# TN_Deck__Display_Board.net
KiCad netlist of a schematic drawn in EAGLE
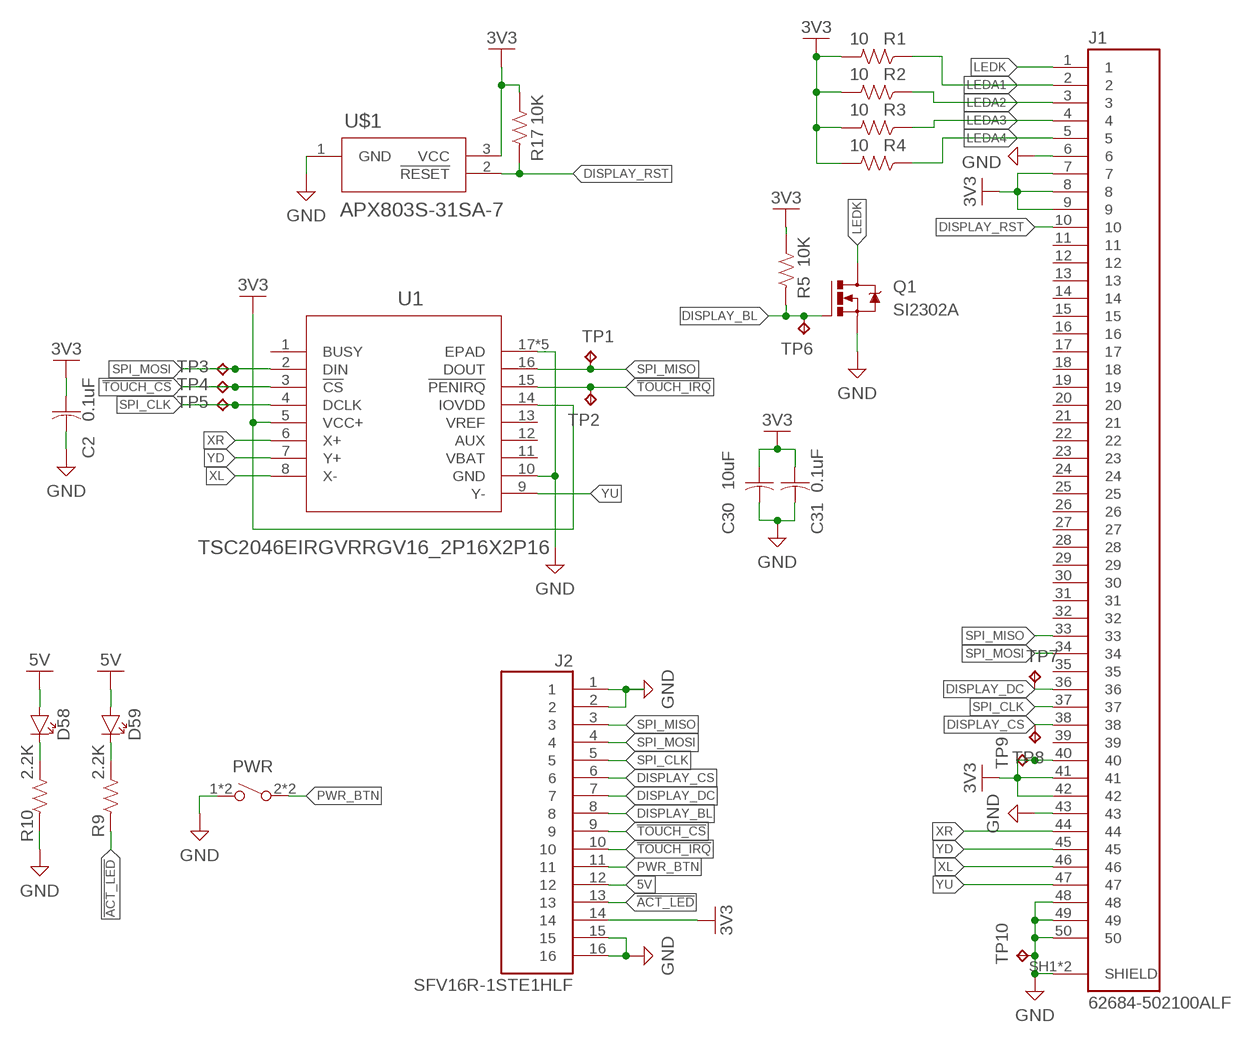
[diagram p0: schematic, sheet 1]

(export (version "E")
  (design (tool "Eeschema 10.0.6"))
  (components
    (comp (ref "C2")
      (value "0.1uF")
      (footprint "eagle-import:CAPC1608X85")
      (fields (field (name "VENDOR") "Digikey") (field (name "VPN") "399-C0603C104K3RACTUCT-ND"))
      (libsource (lib "eagle-import") (part "C-USCHIP-0603(1608-METRIC)_"))
    )
    (comp (ref "C30")
      (value "10uF")
      (footprint "eagle-import:CAPC2012X110")
      (fields (field (name "VENDOR") "Digikey") (field (name "VPN") "1292-0805X106K250CT-ND"))
      (libsource (lib "eagle-import") (part "C-USCHIP-0805(2012-METRIC)_"))
    )
    (comp (ref "C31")
      (value "0.1uF")
      (footprint "eagle-import:CAPC1608X85")
      (fields (field (name "VENDOR") "Digikey") (field (name "VPN") "399-C0603C104K3RACTUCT-ND"))
      (libsource (lib "eagle-import") (part "C-USCHIP-0603(1608-METRIC)_"))
    )
    (comp (ref "D58")
      (value "CHIP-FLAT-G_0603-0.80MM")
      (footprint "eagle-import:LEDC1608X80N_FLAT-G")
      (fields (field (name "VENDOR") "Digikey") (field (name "VPN") "732-4980-1-ND"))
      (libsource (lib "eagle-import") (part "CHIP-FLAT-G_0603-0.80MM"))
    )
    (comp (ref "D59")
      (value "CHIP-FLAT-G_0603-0.80MM")
      (footprint "eagle-import:LEDC1608X80N_FLAT-G")
      (fields (field (name "VENDOR") "Digikey") (field (name "VPN") "732-4980-1-ND"))
      (libsource (lib "eagle-import") (part "CHIP-FLAT-G_0603-0.80MM"))
    )
    (comp (ref "J1")
      (value "62684-502100ALF")
      (footprint "eagle-import:AMPHENOL_62684-502100ALF")
      (fields
        (field (name "MANUFACTURER") "Amphenol")
        (field (name "VENDOR") "Digikey")
        (field (name "VPN") "609-1202-1-ND")
      )
      (libsource (lib "eagle-import") (part "62684-502100ALF"))
    )
    (comp (ref "J2")
      (value "SFV16R-1STE1HLF")
      (footprint "eagle-import:AMPHENOL_SFV16R-1STE1HLF")
      (fields
        (field (name "MANUFACTURER") "Amphenol")
        (field (name "VENDOR") "Digikey")
        (field (name "VPN") "609-4313-1-ND")
      )
      (libsource (lib "eagle-import") (part "SFV16R-1STE1HLF"))
    )
    (comp (ref "PWR")
      (value "SPST-NO_SWITCH_KMR2")
      (footprint "eagle-import:KMR2")
      (fields
        (field (name "MANUFACTURER") "C&K")
        (field (name "MPN") "KMR211G LFS")
        (field (name "VENDOR") "Digikey")
        (field (name "VPN") "401-1426-1-ND")
      )
      (libsource (lib "eagle-import") (part "SPST-NO_SWITCH_KMR2"))
    )
    (comp (ref "Q1")
      (value "SI2302A")
      (footprint "eagle-import:SOT23")
      (fields (field (name "VENDOR") "Digikey") (field (name "VPN") "4518-SI2302ACT-ND"))
      (libsource (lib "eagle-import") (part "NMOSFETSOT23-GSD_"))
    )
    (comp (ref "R1")
      (value "10")
      (footprint "eagle-import:RESC1608X60")
      (fields (field (name "VENDOR") "Digikey") (field (name "VPN") "541-10.0HCT-ND"))
      (libsource (lib "eagle-import") (part "R-USCHIP-0603(1608-METRIC)_"))
    )
    (comp (ref "R2")
      (value "10")
      (footprint "eagle-import:RESC1608X60")
      (fields (field (name "VENDOR") "Digikey") (field (name "VPN") "541-10.0HCT-ND"))
      (libsource (lib "eagle-import") (part "R-USCHIP-0603(1608-METRIC)_"))
    )
    (comp (ref "R3")
      (value "10")
      (footprint "eagle-import:RESC1608X60")
      (fields (field (name "VENDOR") "Digikey") (field (name "VPN") "541-10.0HCT-ND"))
      (libsource (lib "eagle-import") (part "R-USCHIP-0603(1608-METRIC)_"))
    )
    (comp (ref "R4")
      (value "10")
      (footprint "eagle-import:RESC1608X60")
      (fields (field (name "VENDOR") "Digikey") (field (name "VPN") "541-10.0HCT-ND"))
      (libsource (lib "eagle-import") (part "R-USCHIP-0603(1608-METRIC)_"))
    )
    (comp (ref "R5")
      (value "10K")
      (footprint "eagle-import:RESC1608X60")
      (fields (field (name "VENDOR") "Digikey") (field (name "VPN") "541-10.0KHCT-ND"))
      (libsource (lib "eagle-import") (part "R-USCHIP-0603(1608-METRIC)_"))
    )
    (comp (ref "R9")
      (value "2.2K")
      (footprint "eagle-import:RESC1608X60")
      (fields (field (name "VENDOR") "Digikey") (field (name "VPN") "541-2.20KHCT-ND"))
      (libsource (lib "eagle-import") (part "R-USCHIP-0603(1608-METRIC)_"))
    )
    (comp (ref "R10")
      (value "2.2K")
      (footprint "eagle-import:RESC1608X60")
      (fields (field (name "VENDOR") "Digikey") (field (name "VPN") "541-2.20KHCT-ND"))
      (libsource (lib "eagle-import") (part "R-USCHIP-0603(1608-METRIC)_"))
    )
    (comp (ref "R17")
      (value "10K")
      (footprint "eagle-import:RESC1608X60")
      (fields (field (name "VENDOR") "Digikey") (field (name "VPN") "541-10.0KHCT-ND"))
      (libsource (lib "eagle-import") (part "R-USCHIP-0603(1608-METRIC)_"))
    )
    (comp (ref "TP1")
      (value "TPB1,27")
      (footprint "eagle-import:B1,27")
      (libsource (lib "eagle-import") (part "TPB1,27"))
    )
    (comp (ref "TP2")
      (value "TPB1,27")
      (footprint "eagle-import:B1,27")
      (libsource (lib "eagle-import") (part "TPB1,27"))
    )
    (comp (ref "TP3")
      (value "TPB1,27")
      (footprint "eagle-import:B1,27")
      (libsource (lib "eagle-import") (part "TPB1,27"))
    )
    (comp (ref "TP4")
      (value "TPB1,27")
      (footprint "eagle-import:B1,27")
      (libsource (lib "eagle-import") (part "TPB1,27"))
    )
    (comp (ref "TP5")
      (value "TPB1,27")
      (footprint "eagle-import:B1,27")
      (libsource (lib "eagle-import") (part "TPB1,27"))
    )
    (comp (ref "TP6")
      (value "TPB1,27")
      (footprint "eagle-import:B1,27")
      (libsource (lib "eagle-import") (part "TPB1,27"))
    )
    (comp (ref "TP7")
      (value "TPB1,27")
      (footprint "eagle-import:B1,27")
      (libsource (lib "eagle-import") (part "TPB1,27"))
    )
    (comp (ref "TP8")
      (value "TPB1,27")
      (footprint "eagle-import:B1,27")
      (libsource (lib "eagle-import") (part "TPB1,27"))
    )
    (comp (ref "TP9")
      (value "TPB1,27")
      (footprint "eagle-import:B1,27")
      (libsource (lib "eagle-import") (part "TPB1,27"))
    )
    (comp (ref "TP10")
      (value "TPB1,27")
      (footprint "eagle-import:B1,27")
      (libsource (lib "eagle-import") (part "TPB1,27"))
    )
    (comp (ref "U$1")
      (value "APX803S-31SA-7")
      (footprint "eagle-import:SOT-23_DIO")
      (fields (field (name "VENDOR") "Digikey") (field (name "VPN") "APX803S-31SA-7DICT-ND"))
      (libsource (lib "eagle-import") (part "APX803S-31SA-7"))
    )
    (comp (ref "U1")
      (value "TSC2046EIRGVRRGV16_2P16X2P16")
      (footprint "eagle-import:RGV16_2P16X2P16")
      (fields
        (field (name "MANUFACTURER_PART_NUMBER") "TSC2046EIRGVR")
        (field (name "VENDOR") "Digikey")
        (field (name "VPN") "296-46257-1-ND")
        (field (name "COPYRIGHT") "Copyright (C) 2026 Ultra Librarian. All rights reserved.")
      )
      (libsource (lib "eagle-import") (part "TSC2046EIRGVRRGV16_2P16X2P16"))
    )
  )
  (nets
    (net (code "1") (name "/VREF") (class "Default")
      (node (ref "U1") (pin "13") (pinfunction "VREF_13") (pintype "power_in"))
    )
    (net (code "2") (name "/~{ACT_LED}") (class "Default")
      (node (ref "J2") (pin "13") (pinfunction "13_13") (pintype "passive"))
      (node (ref "R9") (pin "1") (pinfunction "1_1") (pintype "passive"))
    )
    (net (code "3") (name "/~{TOUCH_CS}") (class "Default")
      (node (ref "J2") (pin "9") (pinfunction "9_9") (pintype "passive"))
      (node (ref "TP4") (pin "TP") (pinfunction "TP_TP") (pintype "input"))
      (node (ref "U1") (pin "3") (pinfunction "~{CS}_3") (pintype "input"))
    )
    (net (code "4") (name "/~{TOUCH_IRQ}") (class "Default")
      (node (ref "J2") (pin "10") (pinfunction "10_10") (pintype "passive"))
      (node (ref "TP2") (pin "TP") (pinfunction "TP_TP") (pintype "input"))
      (node (ref "U1") (pin "15") (pinfunction "~{PENIRQ}_15") (pintype "input"))
    )
    (net (code "5") (name "3V3") (class "Default")
      (node (ref "C2") (pin "1") (pinfunction "1_1") (pintype "passive"))
      (node (ref "C30") (pin "1") (pinfunction "1_1") (pintype "passive"))
      (node (ref "C31") (pin "1") (pinfunction "1_1") (pintype "passive"))
      (node (ref "J1") (pin "40") (pinfunction "40_40") (pintype "passive"))
      (node (ref "J1") (pin "41") (pinfunction "41_41") (pintype "passive"))
      (node (ref "J1") (pin "42") (pinfunction "42_42") (pintype "passive"))
      (node (ref "J1") (pin "7") (pinfunction "7_7") (pintype "passive"))
      (node (ref "J1") (pin "8") (pinfunction "8_8") (pintype "passive"))
      (node (ref "J1") (pin "9") (pinfunction "9_9") (pintype "passive"))
      (node (ref "J2") (pin "14") (pinfunction "14_14") (pintype "passive"))
      (node (ref "R1") (pin "2") (pinfunction "2_2") (pintype "passive"))
      (node (ref "R17") (pin "2") (pinfunction "2_2") (pintype "passive"))
      (node (ref "R2") (pin "2") (pinfunction "2_2") (pintype "passive"))
      (node (ref "R3") (pin "2") (pinfunction "2_2") (pintype "passive"))
      (node (ref "R4") (pin "2") (pinfunction "2_2") (pintype "passive"))
      (node (ref "R5") (pin "2") (pinfunction "2_2") (pintype "passive"))
      (node (ref "TP9") (pin "TP") (pinfunction "TP_TP") (pintype "input"))
      (node (ref "U$1") (pin "3") (pinfunction "VCC_3") (pintype "power_in"))
      (node (ref "U1") (pin "14") (pinfunction "IOVDD_14") (pintype "bidirectional"))
      (node (ref "U1") (pin "5") (pinfunction "VCC+_5") (pintype "power_in"))
    )
    (net (code "6") (name "5V") (class "Default")
      (node (ref "D58") (pin "A") (pinfunction "A_A") (pintype "passive"))
      (node (ref "D59") (pin "A") (pinfunction "A_A") (pintype "passive"))
      (node (ref "J2") (pin "12") (pinfunction "12_12") (pintype "passive"))
    )
    (net (code "7") (name "DISPLAY_BL") (class "Default")
      (node (ref "J2") (pin "8") (pinfunction "8_8") (pintype "passive"))
      (node (ref "Q1") (pin "1") (pinfunction "G_1") (pintype "passive"))
      (node (ref "R5") (pin "1") (pinfunction "1_1") (pintype "passive"))
      (node (ref "TP6") (pin "TP") (pinfunction "TP_TP") (pintype "input"))
    )
    (net (code "8") (name "DISPLAY_CS") (class "Default")
      (node (ref "J1") (pin "38") (pinfunction "38_38") (pintype "passive"))
      (node (ref "J2") (pin "6") (pinfunction "6_6") (pintype "passive"))
      (node (ref "TP8") (pin "TP") (pinfunction "TP_TP") (pintype "input"))
    )
    (net (code "9") (name "DISPLAY_DC") (class "Default")
      (node (ref "J1") (pin "36") (pinfunction "36_36") (pintype "passive"))
      (node (ref "J2") (pin "7") (pinfunction "7_7") (pintype "passive"))
      (node (ref "TP7") (pin "TP") (pinfunction "TP_TP") (pintype "input"))
    )
    (net (code "10") (name "DISPLAY_RST") (class "Default")
      (node (ref "J1") (pin "10") (pinfunction "10_10") (pintype "passive"))
      (node (ref "R17") (pin "1") (pinfunction "1_1") (pintype "passive"))
      (node (ref "U$1") (pin "2") (pinfunction "~{RESET}_2") (pintype "output"))
    )
    (net (code "11") (name "GND") (class "Default")
      (node (ref "C2") (pin "2") (pinfunction "2_2") (pintype "passive"))
      (node (ref "C30") (pin "2") (pinfunction "2_2") (pintype "passive"))
      (node (ref "C31") (pin "2") (pinfunction "2_2") (pintype "passive"))
      (node (ref "J1") (pin "43") (pinfunction "43_43") (pintype "passive"))
      (node (ref "J1") (pin "48") (pinfunction "48_48") (pintype "passive"))
      (node (ref "J1") (pin "49") (pinfunction "49_49") (pintype "passive"))
      (node (ref "J1") (pin "50") (pinfunction "50_50") (pintype "passive"))
      (node (ref "J1") (pin "6") (pinfunction "6_6") (pintype "passive"))
      (node (ref "J1") (pin "SH1") (pinfunction "SHIELD_SH1") (pintype "passive"))
      (node (ref "J1") (pin "SH2") (pinfunction "SHIELD_SH2") (pintype "passive"))
      (node (ref "J2") (pin "1") (pinfunction "1_1") (pintype "passive"))
      (node (ref "J2") (pin "15") (pinfunction "15_15") (pintype "passive"))
      (node (ref "J2") (pin "16") (pinfunction "16_16") (pintype "passive"))
      (node (ref "J2") (pin "2") (pinfunction "2_2") (pintype "passive"))
      (node (ref "PWR") (pin "1") (pinfunction "1_1") (pintype "passive"))
      (node (ref "PWR") (pin "4") (pinfunction "1_4") (pintype "passive"))
      (node (ref "Q1") (pin "2") (pinfunction "S_2") (pintype "passive"))
      (node (ref "R10") (pin "1") (pinfunction "1_1") (pintype "passive"))
      (node (ref "TP10") (pin "TP") (pinfunction "TP_TP") (pintype "input"))
      (node (ref "U$1") (pin "1") (pinfunction "GND_1") (pintype "power_in"))
      (node (ref "U1") (pin "10") (pinfunction "GND_10") (pintype "power_in"))
      (node (ref "U1") (pin "17") (pinfunction "EPAD_17") (pintype "passive"))
      (node (ref "U1") (pin "V") (pinfunction "EPAD_V") (pintype "passive"))
      (node (ref "U1") (pin "V_1") (pinfunction "EPAD_V_1") (pintype "passive"))
      (node (ref "U1") (pin "V_2") (pinfunction "EPAD_V_2") (pintype "passive"))
      (node (ref "U1") (pin "V_3") (pinfunction "EPAD_V_3") (pintype "passive"))
    )
    (net (code "12") (name "LEDA1") (class "Default")
      (node (ref "J1") (pin "2") (pinfunction "2_2") (pintype "passive"))
      (node (ref "R1") (pin "1") (pinfunction "1_1") (pintype "passive"))
    )
    (net (code "13") (name "LEDA2") (class "Default")
      (node (ref "J1") (pin "3") (pinfunction "3_3") (pintype "passive"))
      (node (ref "R2") (pin "1") (pinfunction "1_1") (pintype "passive"))
    )
    (net (code "14") (name "LEDA3") (class "Default")
      (node (ref "J1") (pin "4") (pinfunction "4_4") (pintype "passive"))
      (node (ref "R3") (pin "1") (pinfunction "1_1") (pintype "passive"))
    )
    (net (code "15") (name "LEDA4") (class "Default")
      (node (ref "J1") (pin "5") (pinfunction "5_5") (pintype "passive"))
      (node (ref "R4") (pin "1") (pinfunction "1_1") (pintype "passive"))
    )
    (net (code "16") (name "LEDK") (class "Default")
      (node (ref "J1") (pin "1") (pinfunction "1_1") (pintype "passive"))
      (node (ref "Q1") (pin "3") (pinfunction "D_3") (pintype "passive"))
    )
    (net (code "17") (name "Net-(D58-PadC)") (class "Default")
      (node (ref "D58") (pin "C") (pinfunction "C_C") (pintype "passive"))
      (node (ref "R10") (pin "2") (pinfunction "2_2") (pintype "passive"))
    )
    (net (code "18") (name "Net-(D59-PadC)") (class "Default")
      (node (ref "D59") (pin "C") (pinfunction "C_C") (pintype "passive"))
      (node (ref "R9") (pin "2") (pinfunction "2_2") (pintype "passive"))
    )
    (net (code "19") (name "PWR_BTN") (class "Default")
      (node (ref "J2") (pin "11") (pinfunction "11_11") (pintype "passive"))
      (node (ref "PWR") (pin "2") (pinfunction "2_2") (pintype "passive"))
      (node (ref "PWR") (pin "3") (pinfunction "2_3") (pintype "passive"))
    )
    (net (code "20") (name "SPI_CLK") (class "Default")
      (node (ref "J1") (pin "37") (pinfunction "37_37") (pintype "passive"))
      (node (ref "J2") (pin "5") (pinfunction "5_5") (pintype "passive"))
      (node (ref "TP5") (pin "TP") (pinfunction "TP_TP") (pintype "input"))
      (node (ref "U1") (pin "4") (pinfunction "DCLK_4") (pintype "input"))
    )
    (net (code "21") (name "SPI_MISO") (class "Default")
      (node (ref "J1") (pin "33") (pinfunction "33_33") (pintype "passive"))
      (node (ref "J2") (pin "3") (pinfunction "3_3") (pintype "passive"))
      (node (ref "TP1") (pin "TP") (pinfunction "TP_TP") (pintype "input"))
      (node (ref "U1") (pin "16") (pinfunction "DOUT_16") (pintype "output"))
    )
    (net (code "22") (name "SPI_MOSI") (class "Default")
      (node (ref "J1") (pin "34") (pinfunction "34_34") (pintype "passive"))
      (node (ref "J2") (pin "4") (pinfunction "4_4") (pintype "passive"))
      (node (ref "TP3") (pin "TP") (pinfunction "TP_TP") (pintype "input"))
      (node (ref "U1") (pin "2") (pinfunction "DIN_2") (pintype "input"))
    )
    (net (code "23") (name "XL") (class "Default")
      (node (ref "J1") (pin "46") (pinfunction "46_46") (pintype "passive"))
      (node (ref "U1") (pin "8") (pinfunction "X-_8") (pintype "input"))
    )
    (net (code "24") (name "XR") (class "Default")
      (node (ref "J1") (pin "44") (pinfunction "44_44") (pintype "passive"))
      (node (ref "U1") (pin "6") (pinfunction "X+_6") (pintype "input"))
    )
    (net (code "25") (name "YD") (class "Default")
      (node (ref "J1") (pin "45") (pinfunction "45_45") (pintype "passive"))
      (node (ref "U1") (pin "7") (pinfunction "Y+_7") (pintype "input"))
    )
    (net (code "26") (name "YU") (class "Default")
      (node (ref "J1") (pin "47") (pinfunction "47_47") (pintype "passive"))
      (node (ref "U1") (pin "9") (pinfunction "Y-_9") (pintype "input"))
    )
    (net (code "27") (name "unconnected-(J1-Pad11)") (class "Default")
      (node (ref "J1") (pin "11") (pinfunction "11_11") (pintype "passive"))
    )
    (net (code "28") (name "unconnected-(J1-Pad12)") (class "Default")
      (node (ref "J1") (pin "12") (pinfunction "12_12") (pintype "passive"))
    )
    (net (code "29") (name "unconnected-(J1-Pad13)") (class "Default")
      (node (ref "J1") (pin "13") (pinfunction "13_13") (pintype "passive"))
    )
    (net (code "30") (name "unconnected-(J1-Pad14)") (class "Default")
      (node (ref "J1") (pin "14") (pinfunction "14_14") (pintype "passive"))
    )
    (net (code "31") (name "unconnected-(J1-Pad15)") (class "Default")
      (node (ref "J1") (pin "15") (pinfunction "15_15") (pintype "passive"))
    )
    (net (code "32") (name "unconnected-(J1-Pad16)") (class "Default")
      (node (ref "J1") (pin "16") (pinfunction "16_16") (pintype "passive"))
    )
    (net (code "33") (name "unconnected-(J1-Pad17)") (class "Default")
      (node (ref "J1") (pin "17") (pinfunction "17_17") (pintype "passive"))
    )
    (net (code "34") (name "unconnected-(J1-Pad18)") (class "Default")
      (node (ref "J1") (pin "18") (pinfunction "18_18") (pintype "passive"))
    )
    (net (code "35") (name "unconnected-(J1-Pad19)") (class "Default")
      (node (ref "J1") (pin "19") (pinfunction "19_19") (pintype "passive"))
    )
    (net (code "36") (name "unconnected-(J1-Pad20)") (class "Default")
      (node (ref "J1") (pin "20") (pinfunction "20_20") (pintype "passive"))
    )
    (net (code "37") (name "unconnected-(J1-Pad21)") (class "Default")
      (node (ref "J1") (pin "21") (pinfunction "21_21") (pintype "passive"))
    )
    (net (code "38") (name "unconnected-(J1-Pad22)") (class "Default")
      (node (ref "J1") (pin "22") (pinfunction "22_22") (pintype "passive"))
    )
    (net (code "39") (name "unconnected-(J1-Pad23)") (class "Default")
      (node (ref "J1") (pin "23") (pinfunction "23_23") (pintype "passive"))
    )
    (net (code "40") (name "unconnected-(J1-Pad24)") (class "Default")
      (node (ref "J1") (pin "24") (pinfunction "24_24") (pintype "passive"))
    )
    (net (code "41") (name "unconnected-(J1-Pad25)") (class "Default")
      (node (ref "J1") (pin "25") (pinfunction "25_25") (pintype "passive"))
    )
    (net (code "42") (name "unconnected-(J1-Pad26)") (class "Default")
      (node (ref "J1") (pin "26") (pinfunction "26_26") (pintype "passive"))
    )
    (net (code "43") (name "unconnected-(J1-Pad27)") (class "Default")
      (node (ref "J1") (pin "27") (pinfunction "27_27") (pintype "passive"))
    )
    (net (code "44") (name "unconnected-(J1-Pad28)") (class "Default")
      (node (ref "J1") (pin "28") (pinfunction "28_28") (pintype "passive"))
    )
    (net (code "45") (name "unconnected-(J1-Pad29)") (class "Default")
      (node (ref "J1") (pin "29") (pinfunction "29_29") (pintype "passive"))
    )
    (net (code "46") (name "unconnected-(J1-Pad30)") (class "Default")
      (node (ref "J1") (pin "30") (pinfunction "30_30") (pintype "passive"))
    )
    (net (code "47") (name "unconnected-(J1-Pad31)") (class "Default")
      (node (ref "J1") (pin "31") (pinfunction "31_31") (pintype "passive"))
    )
    (net (code "48") (name "unconnected-(J1-Pad32)") (class "Default")
      (node (ref "J1") (pin "32") (pinfunction "32_32") (pintype "passive"))
    )
    (net (code "49") (name "unconnected-(J1-Pad35)") (class "Default")
      (node (ref "J1") (pin "35") (pinfunction "35_35") (pintype "passive"))
    )
    (net (code "50") (name "unconnected-(J1-Pad39)") (class "Default")
      (node (ref "J1") (pin "39") (pinfunction "39_39") (pintype "passive"))
    )
    (net (code "51") (name "unconnected-(U1-AUX-Pad12)") (class "Default")
      (node (ref "U1") (pin "12") (pinfunction "AUX_12") (pintype "input"))
    )
    (net (code "52") (name "unconnected-(U1-BUSY-Pad1)") (class "Default")
      (node (ref "U1") (pin "1") (pinfunction "BUSY_1") (pintype "output"))
    )
    (net (code "53") (name "unconnected-(U1-VBAT-Pad11)") (class "Default")
      (node (ref "U1") (pin "11") (pinfunction "VBAT_11") (pintype "input"))
    )
  )
)
